# chaprshield.net
KiCad netlist of a schematic drawn in EAGLE
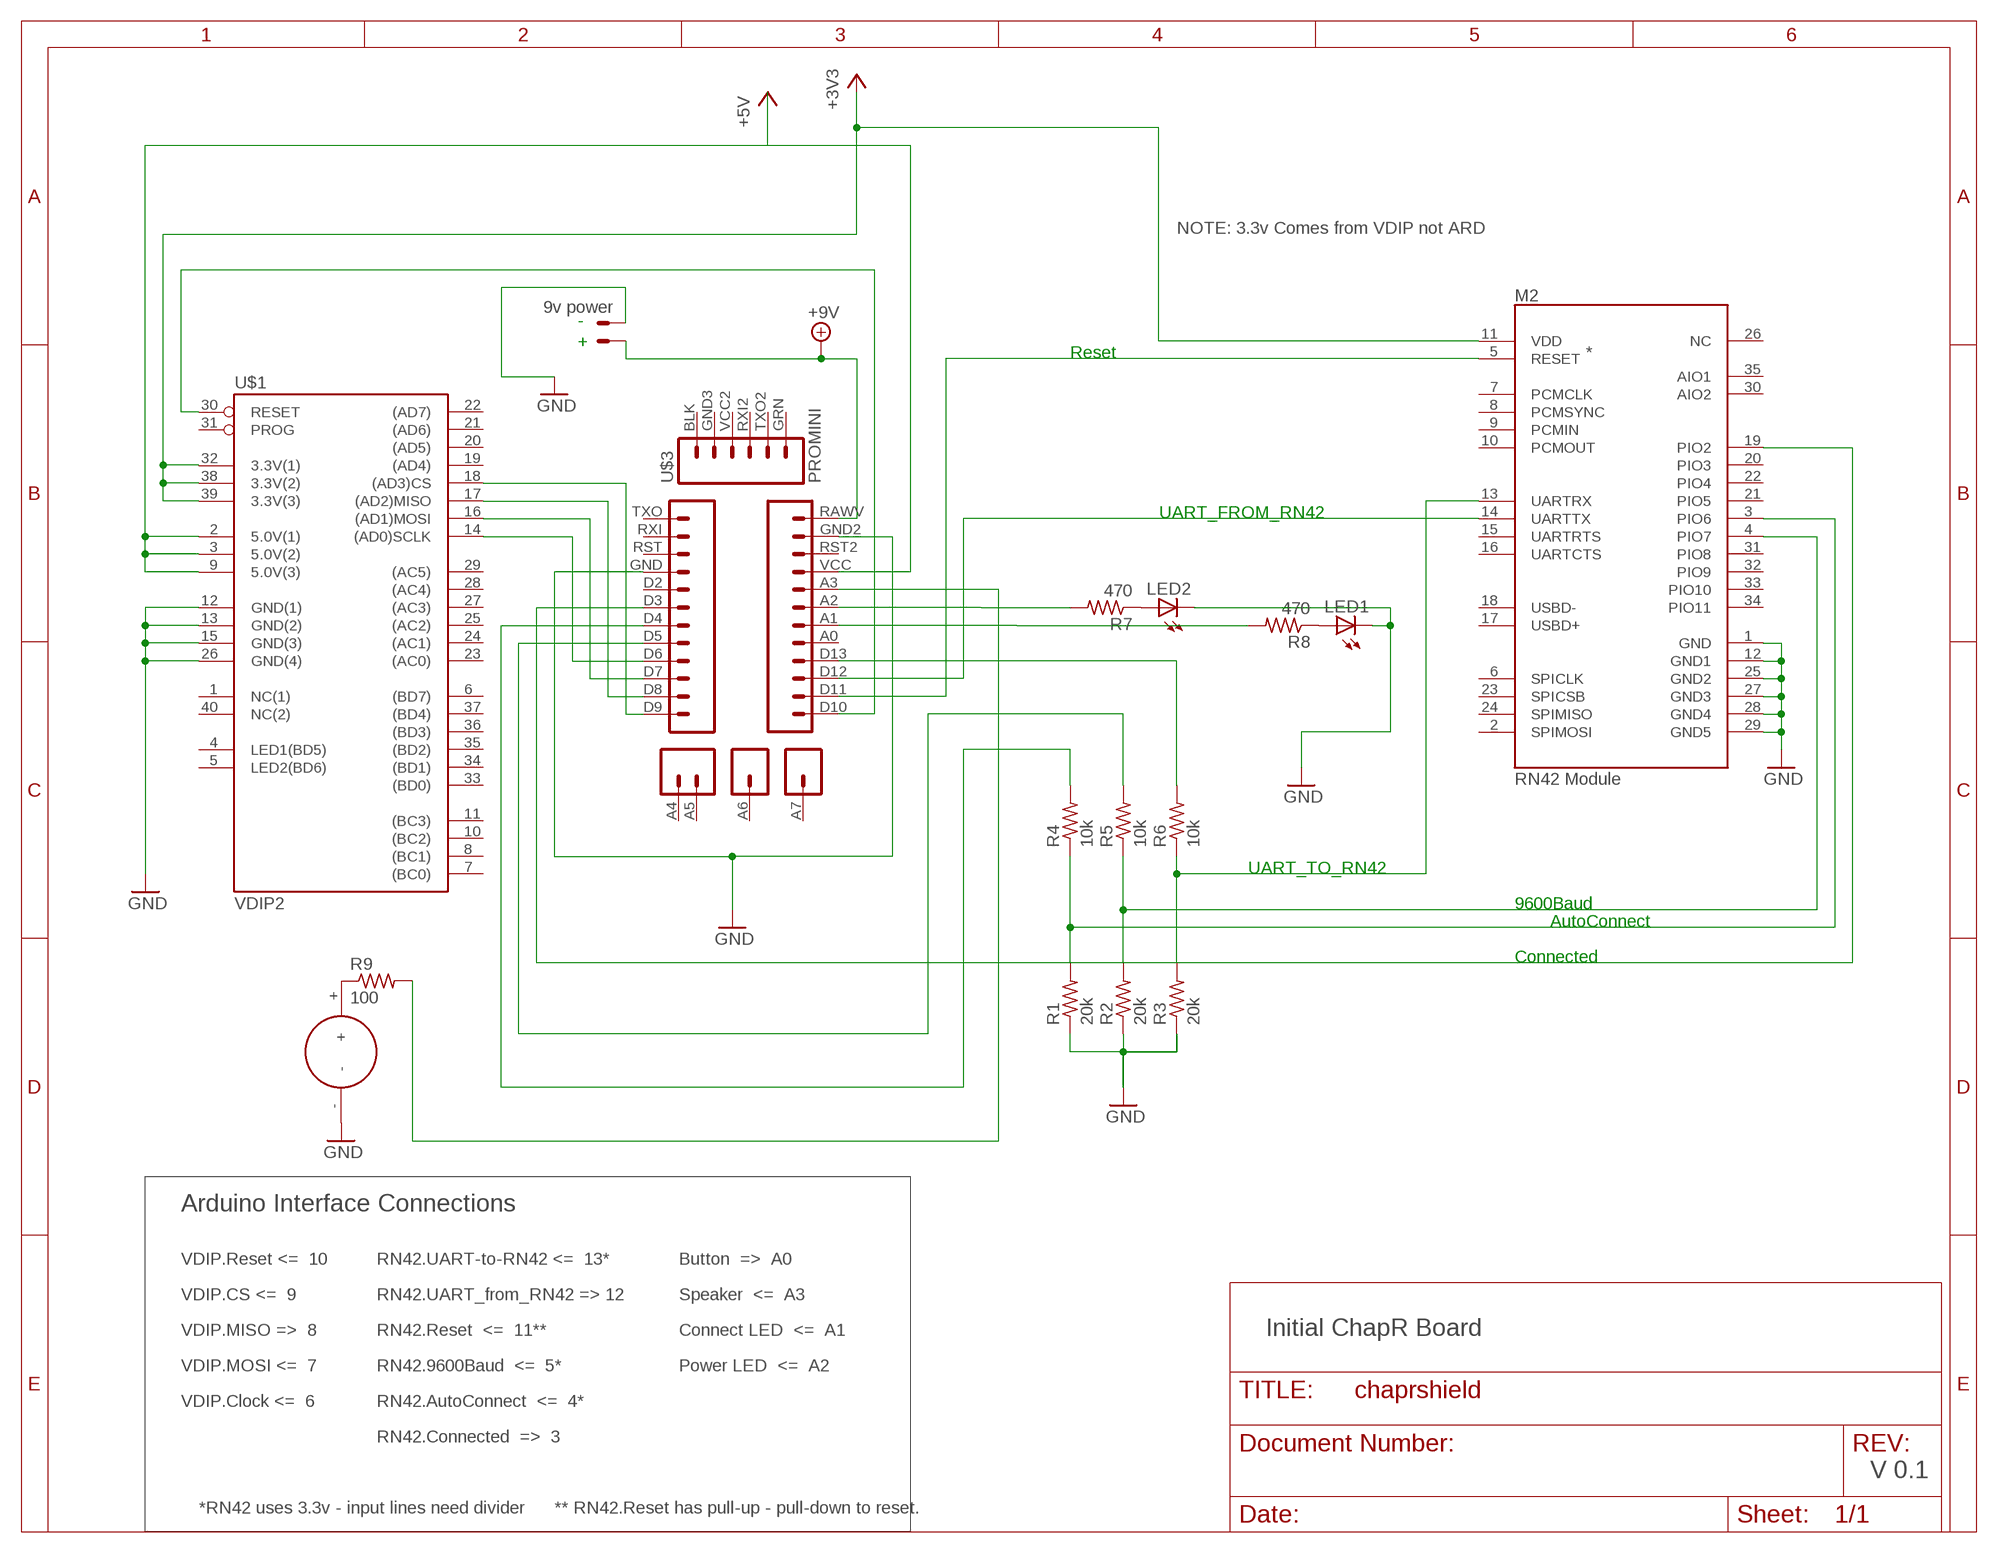
[diagram p0: schematic, sheet 1]

(export (version "E")
  (design (tool "Eeschema 10.0.6"))
  (components
    (comp (ref "-")
      (value "9v power")
      (footprint "eagle-import:22-23-2021")
      (fields (field (name "MF") "MOLEX") (field (name "MPN") "22-23-2021"))
      (libsource (lib "eagle-import") (part "22-23-2021"))
    )
    (comp (ref "LED1")
      (value "LED3MM")
      (footprint "eagle-import:LED3MM")
      (libsource (lib "eagle-import") (part "LED3MM"))
    )
    (comp (ref "LED2")
      (value "LED3MM")
      (footprint "eagle-import:LED3MM")
      (libsource (lib "eagle-import") (part "LED3MM"))
    )
    (comp (ref "M2")
      (value "RN42 Module")
      (footprint "eagle-import:RN41")
      (libsource (lib "eagle-import") (part "BLUETOOTH-RN41{dblquote}"))
    )
    (comp (ref "R1")
      (value "20k")
      (footprint "eagle-import:0207_10")
      (libsource (lib "eagle-import") (part "R-US_0207/10"))
    )
    (comp (ref "R2")
      (value "20k")
      (footprint "eagle-import:0207_10")
      (libsource (lib "eagle-import") (part "R-US_0207/10"))
    )
    (comp (ref "R3")
      (value "20k")
      (footprint "eagle-import:0207_10")
      (libsource (lib "eagle-import") (part "R-US_0207/10"))
    )
    (comp (ref "R4")
      (value "10k")
      (footprint "eagle-import:0207_10")
      (libsource (lib "eagle-import") (part "R-US_0207/10"))
    )
    (comp (ref "R5")
      (value "10k")
      (footprint "eagle-import:0207_10")
      (libsource (lib "eagle-import") (part "R-US_0207/10"))
    )
    (comp (ref "R6")
      (value "10k")
      (footprint "eagle-import:0207_10")
      (libsource (lib "eagle-import") (part "R-US_0207/10"))
    )
    (comp (ref "R7")
      (value "470")
      (footprint "eagle-import:0207_10")
      (libsource (lib "eagle-import") (part "R-US_0207/10"))
    )
    (comp (ref "R8")
      (value "470")
      (footprint "eagle-import:0207_10")
      (libsource (lib "eagle-import") (part "R-US_0207/10"))
    )
    (comp (ref "R9")
      (value "100")
      (footprint "eagle-import:0207_10")
      (libsource (lib "eagle-import") (part "R-US_0207/10"))
    )
    (comp (ref "U$1")
      (value "VDIP2")
      (footprint "eagle-import:VDIP2")
      (libsource (lib "eagle-import") (part "VDIP2"))
    )
    (comp (ref "U$2")
      (value "SPEAKER")
      (footprint "eagle-import:SPEAKER")
      (libsource (lib "eagle-import") (part "SPEAKER"))
    )
    (comp (ref "U$3")
      (value "PROMINI")
      (footprint "eagle-import:PROMINI")
      (libsource (lib "eagle-import") (part "PROMINI"))
    )
  )
  (nets
    (net (code "1") (name "+3V3") (class "Default")
      (node (ref "M2") (pin "11") (pinfunction "VDD_11") (pintype "bidirectional"))
      (node (ref "U$1") (pin "32") (pinfunction "3.3V(1)_32") (pintype "input"))
      (node (ref "U$1") (pin "38") (pinfunction "3.3V(2)_38") (pintype "power_in"))
      (node (ref "U$1") (pin "39") (pinfunction "3.3V(3)_39") (pintype "input"))
    )
    (net (code "3") (name "+9V") (class "Default")
      (node (ref "-") (pin "2") (pinfunction "S_2") (pintype "passive"))
      (node (ref "U$3") (pin "RAWV") (pinfunction "RAWV_RAWV") (pintype "passive"))
    )
    (net (code "4") (name "/LED1(BD5)") (class "Default")
      (node (ref "U$1") (pin "4") (pinfunction "LED1(BD5)_4") (pintype "power_in"))
    )
    (net (code "5") (name "/LED2(BD6)") (class "Default")
      (node (ref "U$1") (pin "5") (pinfunction "LED2(BD6)_5") (pintype "power_in"))
    )
    (net (code "6") (name "/NC(1)") (class "Default")
      (node (ref "U$1") (pin "1") (pinfunction "NC(1)_1") (pintype "power_in"))
    )
    (net (code "7") (name "/NC(2)") (class "Default")
      (node (ref "U$1") (pin "40") (pinfunction "NC(2)_40") (pintype "power_in"))
    )
    (net (code "8") (name "GND") (class "Default")
      (node (ref "-") (pin "1") (pinfunction "S_1") (pintype "passive"))
      (node (ref "LED1") (pin "K") (pinfunction "C_K") (pintype "passive"))
      (node (ref "LED2") (pin "K") (pinfunction "C_K") (pintype "passive"))
      (node (ref "M2") (pin "1") (pinfunction "GND_1") (pintype "bidirectional"))
      (node (ref "M2") (pin "12") (pinfunction "GND1_12") (pintype "bidirectional"))
      (node (ref "M2") (pin "25") (pinfunction "GND2_25") (pintype "bidirectional"))
      (node (ref "M2") (pin "27") (pinfunction "GND3_27") (pintype "bidirectional"))
      (node (ref "M2") (pin "28") (pinfunction "GND4_28") (pintype "bidirectional"))
      (node (ref "M2") (pin "29") (pinfunction "GND5_29") (pintype "bidirectional"))
      (node (ref "R1") (pin "1") (pinfunction "1_1") (pintype "passive"))
      (node (ref "R2") (pin "1") (pinfunction "1_1") (pintype "passive"))
      (node (ref "R3") (pin "1") (pinfunction "1_1") (pintype "passive"))
      (node (ref "U$1") (pin "12") (pinfunction "GND(1)_12") (pintype "power_in"))
      (node (ref "U$1") (pin "13") (pinfunction "GND(2)_13") (pintype "power_in"))
      (node (ref "U$1") (pin "15") (pinfunction "GND(3)_15") (pintype "power_in"))
      (node (ref "U$1") (pin "26") (pinfunction "GND(4)_26") (pintype "power_in"))
      (node (ref "U$2") (pin "-") (pinfunction "-_-") (pintype "bidirectional"))
      (node (ref "U$3") (pin "GND") (pinfunction "GND_GND") (pintype "passive"))
      (node (ref "U$3") (pin "GND2") (pinfunction "GND2_GND2") (pintype "passive"))
    )
    (net (code "9") (name "Net-(LED1-PadA)") (class "Default")
      (node (ref "LED1") (pin "A") (pinfunction "A_A") (pintype "passive"))
      (node (ref "R8") (pin "1") (pinfunction "1_1") (pintype "passive"))
    )
    (net (code "10") (name "Net-(LED2-PadA)") (class "Default")
      (node (ref "LED2") (pin "A") (pinfunction "A_A") (pintype "passive"))
      (node (ref "R7") (pin "1") (pinfunction "1_1") (pintype "passive"))
    )
    (net (code "11") (name "Net-(M2-PIO2)") (class "Default")
      (node (ref "M2") (pin "19") (pinfunction "PIO2_19") (pintype "bidirectional"))
      (node (ref "U$3") (pin "D3") (pinfunction "D3_D3") (pintype "passive"))
    )
    (net (code "12") (name "Net-(M2-PIO6)") (class "Default")
      (node (ref "M2") (pin "3") (pinfunction "PIO6_3") (pintype "bidirectional"))
      (node (ref "R1") (pin "2") (pinfunction "2_2") (pintype "passive"))
      (node (ref "R4") (pin "1") (pinfunction "1_1") (pintype "passive"))
    )
    (net (code "13") (name "Net-(M2-PIO7)") (class "Default")
      (node (ref "M2") (pin "4") (pinfunction "PIO7_4") (pintype "bidirectional"))
      (node (ref "R2") (pin "2") (pinfunction "2_2") (pintype "passive"))
      (node (ref "R5") (pin "1") (pinfunction "1_1") (pintype "passive"))
    )
    (net (code "14") (name "Net-(M2-RESET)") (class "Default")
      (node (ref "M2") (pin "5") (pinfunction "RESET_5") (pintype "bidirectional"))
      (node (ref "U$3") (pin "D11") (pinfunction "D11_D11") (pintype "passive"))
    )
    (net (code "15") (name "Net-(M2-UARTRX)") (class "Default")
      (node (ref "M2") (pin "13") (pinfunction "UARTRX_13") (pintype "bidirectional"))
      (node (ref "R3") (pin "2") (pinfunction "2_2") (pintype "passive"))
      (node (ref "R6") (pin "1") (pinfunction "1_1") (pintype "passive"))
    )
    (net (code "16") (name "Net-(M2-UARTTX)") (class "Default")
      (node (ref "M2") (pin "14") (pinfunction "UARTTX_14") (pintype "bidirectional"))
      (node (ref "U$3") (pin "D12") (pinfunction "D12_D12") (pintype "passive"))
    )
    (net (code "17") (name "Net-(R4-Pad2)") (class "Default")
      (node (ref "R4") (pin "2") (pinfunction "2_2") (pintype "passive"))
      (node (ref "U$3") (pin "D4") (pinfunction "D4_D4") (pintype "passive"))
    )
    (net (code "18") (name "Net-(R5-Pad2)") (class "Default")
      (node (ref "R5") (pin "2") (pinfunction "2_2") (pintype "passive"))
      (node (ref "U$3") (pin "D5") (pinfunction "D5_D5") (pintype "passive"))
    )
    (net (code "19") (name "Net-(R6-Pad2)") (class "Default")
      (node (ref "R6") (pin "2") (pinfunction "2_2") (pintype "passive"))
      (node (ref "U$3") (pin "D13") (pinfunction "D13_D13") (pintype "passive"))
    )
    (net (code "20") (name "Net-(R7-Pad2)") (class "Default")
      (node (ref "R7") (pin "2") (pinfunction "2_2") (pintype "passive"))
      (node (ref "U$3") (pin "A2") (pinfunction "A2_A2") (pintype "passive"))
    )
    (net (code "21") (name "Net-(R8-Pad2)") (class "Default")
      (node (ref "R8") (pin "2") (pinfunction "2_2") (pintype "passive"))
      (node (ref "U$3") (pin "A1") (pinfunction "A1_A1") (pintype "passive"))
    )
    (net (code "22") (name "Net-(R9-Pad1)") (class "Default")
      (node (ref "R9") (pin "1") (pinfunction "1_1") (pintype "passive"))
      (node (ref "U$2") (pin "+") (pinfunction "+_+") (pintype "bidirectional"))
    )
    (net (code "23") (name "Net-(R9-Pad2)") (class "Default")
      (node (ref "R9") (pin "2") (pinfunction "2_2") (pintype "passive"))
      (node (ref "U$3") (pin "A3") (pinfunction "A3_A3") (pintype "passive"))
    )
    (net (code "24") (name "Net-(U$1-(AD0)SCLK)") (class "Default")
      (node (ref "U$1") (pin "14") (pinfunction "(AD0)SCLK_14") (pintype "bidirectional"))
      (node (ref "U$3") (pin "D6") (pinfunction "D6_D6") (pintype "passive"))
    )
    (net (code "25") (name "Net-(U$1-(AD1)MOSI)") (class "Default")
      (node (ref "U$1") (pin "16") (pinfunction "(AD1)MOSI_16") (pintype "bidirectional"))
      (node (ref "U$3") (pin "D7") (pinfunction "D7_D7") (pintype "passive"))
    )
    (net (code "26") (name "Net-(U$1-(AD2)MISO)") (class "Default")
      (node (ref "U$1") (pin "17") (pinfunction "(AD2)MISO_17") (pintype "bidirectional"))
      (node (ref "U$3") (pin "D8") (pinfunction "D8_D8") (pintype "passive"))
    )
    (net (code "27") (name "Net-(U$1-(AD3)CS)") (class "Default")
      (node (ref "U$1") (pin "18") (pinfunction "(AD3)CS_18") (pintype "bidirectional"))
      (node (ref "U$3") (pin "D9") (pinfunction "D9_D9") (pintype "passive"))
    )
    (net (code "28") (name "Net-(U$1-5.0V(1))") (class "Default")
      (node (ref "U$1") (pin "2") (pinfunction "5.0V(1)_2") (pintype "power_in"))
      (node (ref "U$1") (pin "3") (pinfunction "5.0V(2)_3") (pintype "power_in"))
      (node (ref "U$1") (pin "9") (pinfunction "5.0V(3)_9") (pintype "power_in"))
      (node (ref "U$3") (pin "VCC") (pinfunction "VCC_VCC") (pintype "passive"))
    )
    (net (code "29") (name "Net-(U$1-RESET)") (class "Default")
      (node (ref "U$1") (pin "30") (pinfunction "RESET_30") (pintype "input"))
      (node (ref "U$3") (pin "D10") (pinfunction "D10_D10") (pintype "passive"))
    )
    (net (code "30") (name "unconnected-(M2-AIO1-Pad35)") (class "Default")
      (node (ref "M2") (pin "35") (pinfunction "AIO1_35") (pintype "bidirectional"))
    )
    (net (code "31") (name "unconnected-(M2-AIO2-Pad30)") (class "Default")
      (node (ref "M2") (pin "30") (pinfunction "AIO2_30") (pintype "bidirectional"))
    )
    (net (code "32") (name "unconnected-(M2-NC-Pad26)") (class "Default")
      (node (ref "M2") (pin "26") (pinfunction "NC_26") (pintype "bidirectional"))
    )
    (net (code "33") (name "unconnected-(M2-PCMCLK-Pad7)") (class "Default")
      (node (ref "M2") (pin "7") (pinfunction "PCMCLK_7") (pintype "bidirectional"))
    )
    (net (code "34") (name "unconnected-(M2-PCMIN-Pad9)") (class "Default")
      (node (ref "M2") (pin "9") (pinfunction "PCMIN_9") (pintype "bidirectional"))
    )
    (net (code "35") (name "unconnected-(M2-PCMOUT-Pad10)") (class "Default")
      (node (ref "M2") (pin "10") (pinfunction "PCMOUT_10") (pintype "bidirectional"))
    )
    (net (code "36") (name "unconnected-(M2-PCMSYNC-Pad8)") (class "Default")
      (node (ref "M2") (pin "8") (pinfunction "PCMSYNC_8") (pintype "bidirectional"))
    )
    (net (code "37") (name "unconnected-(M2-PIO3-Pad20)") (class "Default")
      (node (ref "M2") (pin "20") (pinfunction "PIO3_20") (pintype "bidirectional"))
    )
    (net (code "38") (name "unconnected-(M2-PIO4-Pad22)") (class "Default")
      (node (ref "M2") (pin "22") (pinfunction "PIO4_22") (pintype "bidirectional"))
    )
    (net (code "39") (name "unconnected-(M2-PIO5-Pad21)") (class "Default")
      (node (ref "M2") (pin "21") (pinfunction "PIO5_21") (pintype "bidirectional"))
    )
    (net (code "40") (name "unconnected-(M2-PIO8-Pad31)") (class "Default")
      (node (ref "M2") (pin "31") (pinfunction "PIO8_31") (pintype "bidirectional"))
    )
    (net (code "41") (name "unconnected-(M2-PIO9-Pad32)") (class "Default")
      (node (ref "M2") (pin "32") (pinfunction "PIO9_32") (pintype "bidirectional"))
    )
    (net (code "42") (name "unconnected-(M2-PIO10-Pad33)") (class "Default")
      (node (ref "M2") (pin "33") (pinfunction "PIO10_33") (pintype "bidirectional"))
    )
    (net (code "43") (name "unconnected-(M2-PIO11-Pad34)") (class "Default")
      (node (ref "M2") (pin "34") (pinfunction "PIO11_34") (pintype "bidirectional"))
    )
    (net (code "44") (name "unconnected-(M2-SPICLK-Pad6)") (class "Default")
      (node (ref "M2") (pin "6") (pinfunction "SPICLK_6") (pintype "bidirectional"))
    )
    (net (code "45") (name "unconnected-(M2-SPICSB-Pad23)") (class "Default")
      (node (ref "M2") (pin "23") (pinfunction "SPICSB_23") (pintype "bidirectional"))
    )
    (net (code "46") (name "unconnected-(M2-SPIMISO-Pad24)") (class "Default")
      (node (ref "M2") (pin "24") (pinfunction "SPIMISO_24") (pintype "bidirectional"))
    )
    (net (code "47") (name "unconnected-(M2-SPIMOSI-Pad2)") (class "Default")
      (node (ref "M2") (pin "2") (pinfunction "SPIMOSI_2") (pintype "bidirectional"))
    )
    (net (code "48") (name "unconnected-(M2-UARTCTS-Pad16)") (class "Default")
      (node (ref "M2") (pin "16") (pinfunction "UARTCTS_16") (pintype "bidirectional"))
    )
    (net (code "49") (name "unconnected-(M2-UARTRTS-Pad15)") (class "Default")
      (node (ref "M2") (pin "15") (pinfunction "UARTRTS_15") (pintype "bidirectional"))
    )
    (net (code "50") (name "unconnected-(M2-USBD+-Pad17)") (class "Default")
      (node (ref "M2") (pin "17") (pinfunction "USBD+_17") (pintype "bidirectional"))
    )
    (net (code "51") (name "unconnected-(M2-USBD--Pad18)") (class "Default")
      (node (ref "M2") (pin "18") (pinfunction "USBD-_18") (pintype "bidirectional"))
    )
    (net (code "52") (name "unconnected-(U$1-(AC0)-Pad23)") (class "Default")
      (node (ref "U$1") (pin "23") (pinfunction "(AC0)_23") (pintype "bidirectional"))
    )
    (net (code "53") (name "unconnected-(U$1-(AC1)-Pad24)") (class "Default")
      (node (ref "U$1") (pin "24") (pinfunction "(AC1)_24") (pintype "bidirectional"))
    )
    (net (code "54") (name "unconnected-(U$1-(AC2)-Pad25)") (class "Default")
      (node (ref "U$1") (pin "25") (pinfunction "(AC2)_25") (pintype "bidirectional"))
    )
    (net (code "55") (name "unconnected-(U$1-(AC3)-Pad27)") (class "Default")
      (node (ref "U$1") (pin "27") (pinfunction "(AC3)_27") (pintype "bidirectional"))
    )
    (net (code "56") (name "unconnected-(U$1-(AC4)-Pad28)") (class "Default")
      (node (ref "U$1") (pin "28") (pinfunction "(AC4)_28") (pintype "bidirectional"))
    )
    (net (code "57") (name "unconnected-(U$1-(AC5)-Pad29)") (class "Default")
      (node (ref "U$1") (pin "29") (pinfunction "(AC5)_29") (pintype "bidirectional"))
    )
    (net (code "58") (name "unconnected-(U$1-(AD4)-Pad19)") (class "Default")
      (node (ref "U$1") (pin "19") (pinfunction "(AD4)_19") (pintype "bidirectional"))
    )
    (net (code "59") (name "unconnected-(U$1-(AD5)-Pad20)") (class "Default")
      (node (ref "U$1") (pin "20") (pinfunction "(AD5)_20") (pintype "bidirectional"))
    )
    (net (code "60") (name "unconnected-(U$1-(AD6)-Pad21)") (class "Default")
      (node (ref "U$1") (pin "21") (pinfunction "(AD6)_21") (pintype "bidirectional"))
    )
    (net (code "61") (name "unconnected-(U$1-(AD7)-Pad22)") (class "Default")
      (node (ref "U$1") (pin "22") (pinfunction "(AD7)_22") (pintype "bidirectional"))
    )
    (net (code "62") (name "unconnected-(U$1-(BC0)-Pad7)") (class "Default")
      (node (ref "U$1") (pin "7") (pinfunction "(BC0)_7") (pintype "bidirectional"))
    )
    (net (code "63") (name "unconnected-(U$1-(BC1)-Pad8)") (class "Default")
      (node (ref "U$1") (pin "8") (pinfunction "(BC1)_8") (pintype "bidirectional"))
    )
    (net (code "64") (name "unconnected-(U$1-(BC2)-Pad10)") (class "Default")
      (node (ref "U$1") (pin "10") (pinfunction "(BC2)_10") (pintype "bidirectional"))
    )
    (net (code "65") (name "unconnected-(U$1-(BC3)-Pad11)") (class "Default")
      (node (ref "U$1") (pin "11") (pinfunction "(BC3)_11") (pintype "bidirectional"))
    )
    (net (code "66") (name "unconnected-(U$1-(BD0)-Pad33)") (class "Default")
      (node (ref "U$1") (pin "33") (pinfunction "(BD0)_33") (pintype "bidirectional"))
    )
    (net (code "67") (name "unconnected-(U$1-(BD1)-Pad34)") (class "Default")
      (node (ref "U$1") (pin "34") (pinfunction "(BD1)_34") (pintype "bidirectional"))
    )
    (net (code "68") (name "unconnected-(U$1-(BD2)-Pad35)") (class "Default")
      (node (ref "U$1") (pin "35") (pinfunction "(BD2)_35") (pintype "bidirectional"))
    )
    (net (code "69") (name "unconnected-(U$1-(BD3)-Pad36)") (class "Default")
      (node (ref "U$1") (pin "36") (pinfunction "(BD3)_36") (pintype "bidirectional"))
    )
    (net (code "70") (name "unconnected-(U$1-(BD4)-Pad37)") (class "Default")
      (node (ref "U$1") (pin "37") (pinfunction "(BD4)_37") (pintype "bidirectional"))
    )
    (net (code "71") (name "unconnected-(U$1-(BD7)-Pad6)") (class "Default")
      (node (ref "U$1") (pin "6") (pinfunction "(BD7)_6") (pintype "bidirectional"))
    )
    (net (code "72") (name "unconnected-(U$1-PROG-Pad31)") (class "Default")
      (node (ref "U$1") (pin "31") (pinfunction "PROG_31") (pintype "input"))
    )
    (net (code "73") (name "unconnected-(U$3-PadA0)") (class "Default")
      (node (ref "U$3") (pin "A0") (pinfunction "A0_A0") (pintype "passive"))
    )
    (net (code "74") (name "unconnected-(U$3-PadA4)") (class "Default")
      (node (ref "U$3") (pin "A4") (pinfunction "A4_A4") (pintype "passive"))
    )
    (net (code "75") (name "unconnected-(U$3-PadA5)") (class "Default")
      (node (ref "U$3") (pin "A5") (pinfunction "A5_A5") (pintype "passive"))
    )
    (net (code "76") (name "unconnected-(U$3-PadA6)") (class "Default")
      (node (ref "U$3") (pin "A6") (pinfunction "A6_A6") (pintype "passive"))
    )
    (net (code "77") (name "unconnected-(U$3-PadA7)") (class "Default")
      (node (ref "U$3") (pin "A7") (pinfunction "A7_A7") (pintype "passive"))
    )
    (net (code "78") (name "unconnected-(U$3-PadBLK)") (class "Default")
      (node (ref "U$3") (pin "BLK") (pinfunction "BLK_BLK") (pintype "passive"))
    )
    (net (code "79") (name "unconnected-(U$3-PadD2)") (class "Default")
      (node (ref "U$3") (pin "D2") (pinfunction "D2_D2") (pintype "passive"))
    )
    (net (code "80") (name "unconnected-(U$3-PadGND3)") (class "Default")
      (node (ref "U$3") (pin "GND3") (pinfunction "GND3_GND3") (pintype "passive"))
    )
    (net (code "81") (name "unconnected-(U$3-PadGRN)") (class "Default")
      (node (ref "U$3") (pin "GRN") (pinfunction "GRN_GRN") (pintype "passive"))
    )
    (net (code "82") (name "unconnected-(U$3-PadRST)") (class "Default")
      (node (ref "U$3") (pin "RST") (pinfunction "RST_RST") (pintype "passive"))
    )
    (net (code "83") (name "unconnected-(U$3-PadRST2)") (class "Default")
      (node (ref "U$3") (pin "RST2") (pinfunction "RST2_RST2") (pintype "passive"))
    )
    (net (code "84") (name "unconnected-(U$3-PadRXI)") (class "Default")
      (node (ref "U$3") (pin "RXI") (pinfunction "RXI_RXI") (pintype "passive"))
    )
    (net (code "85") (name "unconnected-(U$3-PadRXI2)") (class "Default")
      (node (ref "U$3") (pin "RXI2") (pinfunction "RXI2_RXI2") (pintype "passive"))
    )
    (net (code "86") (name "unconnected-(U$3-PadTXO)") (class "Default")
      (node (ref "U$3") (pin "TXO") (pinfunction "TXO_TXO") (pintype "passive"))
    )
    (net (code "87") (name "unconnected-(U$3-PadTXO2)") (class "Default")
      (node (ref "U$3") (pin "TXO2") (pinfunction "TXO2_TXO2") (pintype "passive"))
    )
    (net (code "88") (name "unconnected-(U$3-PadVCC2)") (class "Default")
      (node (ref "U$3") (pin "VCC2") (pinfunction "VCC2_VCC2") (pintype "passive"))
    )
  )
)
